# belt_output.net
KiCad netlist of a schematic drawn in Altium Designer
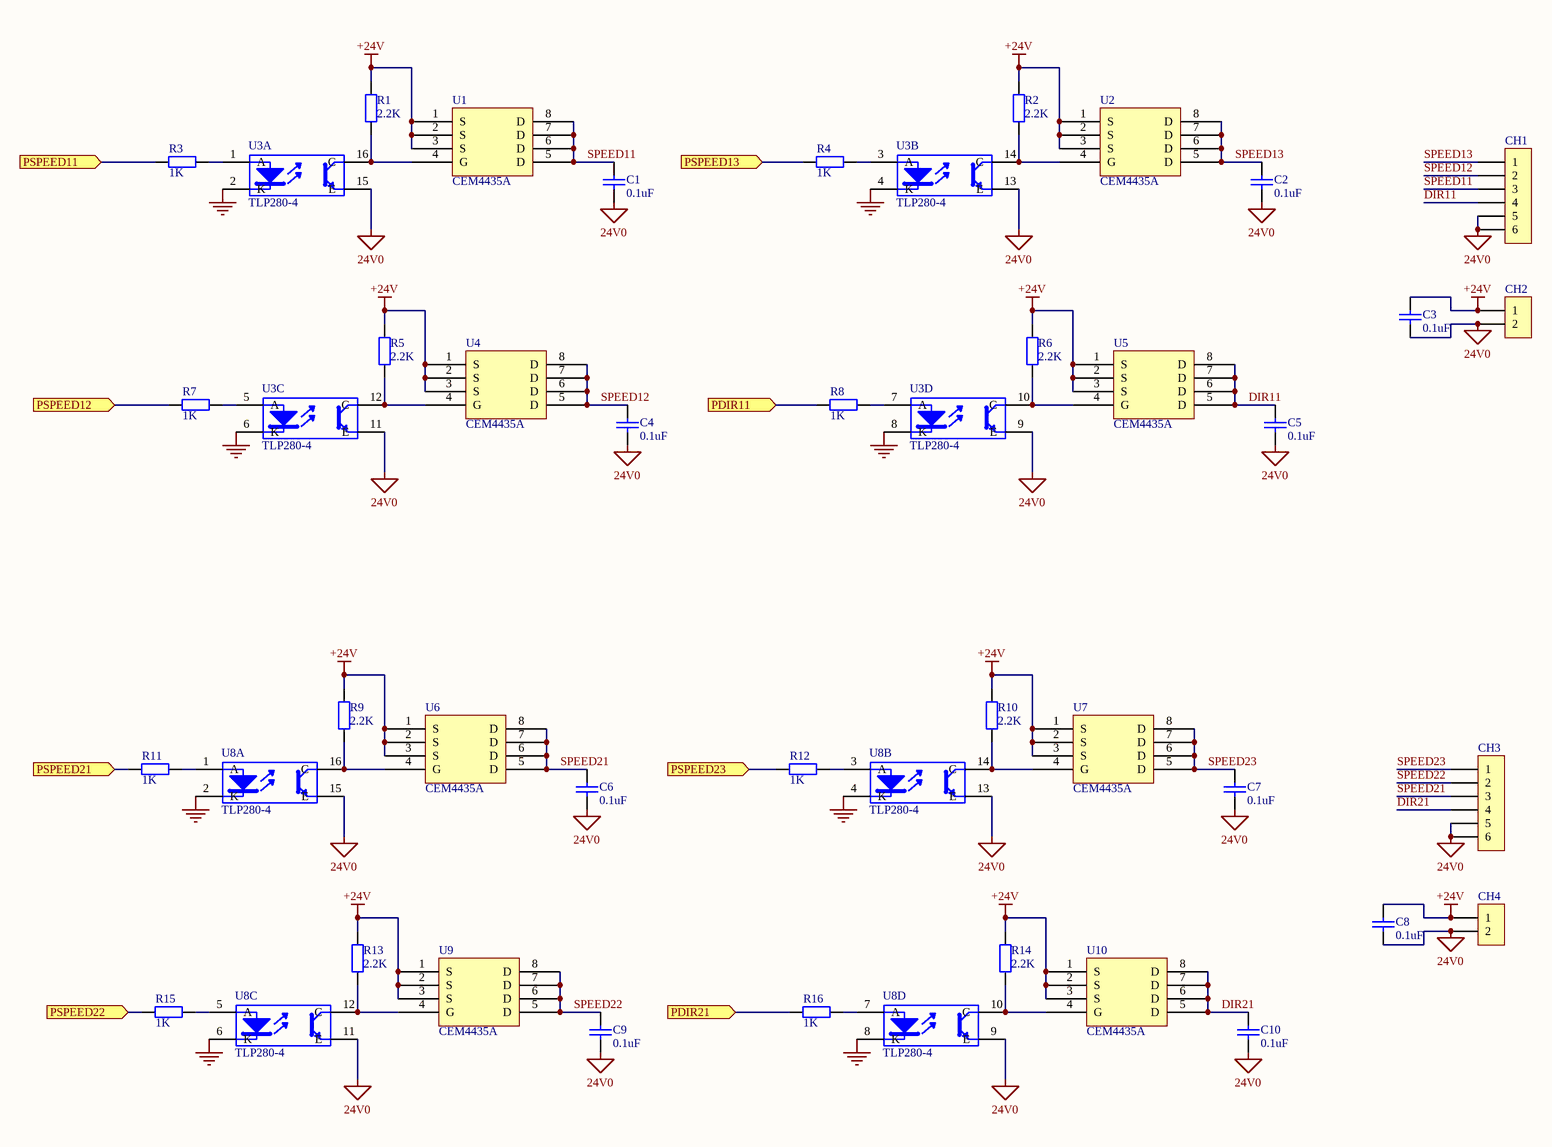
[diagram p0: belt_output.SchDoc]

(export (version "E")
  (design (tool "Eeschema 10.0.6"))
  (components
    (comp (ref "C1")
      (value "0.1uF")
      (footprint "0805")
      (description "Capacitor")
      (fields (field (name "Comment") "Cap") (field (name "PUBLISHER") "Altium Limited"))
      (libsource (lib "Miscellaneous Devices") (part "Cap"))
    )
    (comp (ref "C2")
      (value "0.1uF")
      (footprint "0805")
      (description "Capacitor")
      (fields (field (name "Comment") "Cap") (field (name "PUBLISHER") "Altium Limited"))
      (libsource (lib "Miscellaneous Devices") (part "Cap"))
    )
    (comp (ref "C3")
      (value "0.1uF")
      (footprint "0805")
      (description "Capacitor")
      (fields (field (name "Comment") "Cap") (field (name "PUBLISHER") "Altium Limited"))
      (libsource (lib "Miscellaneous Devices") (part "Cap"))
    )
    (comp (ref "C4")
      (value "0.1uF")
      (footprint "0805")
      (description "Capacitor")
      (fields (field (name "Comment") "Cap") (field (name "PUBLISHER") "Altium Limited"))
      (libsource (lib "Miscellaneous Devices") (part "Cap"))
    )
    (comp (ref "C5")
      (value "0.1uF")
      (footprint "0805")
      (description "Capacitor")
      (fields (field (name "Comment") "Cap") (field (name "PUBLISHER") "Altium Limited"))
      (libsource (lib "Miscellaneous Devices") (part "Cap"))
    )
    (comp (ref "C6")
      (value "0.1uF")
      (footprint "0805")
      (description "Capacitor")
      (fields (field (name "Comment") "Cap") (field (name "PUBLISHER") "Altium Limited"))
      (libsource (lib "Miscellaneous Devices") (part "Cap"))
    )
    (comp (ref "C7")
      (value "0.1uF")
      (footprint "0805")
      (description "Capacitor")
      (fields (field (name "Comment") "Cap") (field (name "PUBLISHER") "Altium Limited"))
      (libsource (lib "Miscellaneous Devices") (part "Cap"))
    )
    (comp (ref "C8")
      (value "0.1uF")
      (footprint "0805")
      (description "Capacitor")
      (fields (field (name "Comment") "Cap") (field (name "PUBLISHER") "Altium Limited"))
      (libsource (lib "Miscellaneous Devices") (part "Cap"))
    )
    (comp (ref "C9")
      (value "0.1uF")
      (footprint "0805")
      (description "Capacitor")
      (fields (field (name "Comment") "Cap") (field (name "PUBLISHER") "Altium Limited"))
      (libsource (lib "Miscellaneous Devices") (part "Cap"))
    )
    (comp (ref "C10")
      (value "0.1uF")
      (footprint "0805")
      (description "Capacitor")
      (fields (field (name "Comment") "Cap") (field (name "PUBLISHER") "Altium Limited"))
      (libsource (lib "Miscellaneous Devices") (part "Cap"))
    )
    (comp (ref "CH1")
      (value "HEADER1X6")
      (footprint "CH3.96-6PIN")
      (libsource (lib "myIntegrated_Library1") (part "HEADER1X6"))
    )
    (comp (ref "CH2")
      (value "HEADER1X2")
      (footprint "CH3.96-2PIN")
      (libsource (lib "myIntegrated_Library1") (part "HEADER1X2"))
    )
    (comp (ref "CH3")
      (value "HEADER1X6")
      (footprint "CH3.96-6PIN")
      (libsource (lib "myIntegrated_Library1") (part "HEADER1X6"))
    )
    (comp (ref "CH4")
      (value "HEADER1X2")
      (footprint "CH3.96-2PIN")
      (libsource (lib "myIntegrated_Library1") (part "HEADER1X2"))
    )
    (comp (ref "R1")
      (value "2.2K")
      (footprint "0805")
      (description "Resistor")
      (fields (field (name "Comment") "Res2") (field (name "PUBLISHER") "Altium Limited"))
      (libsource (lib "Miscellaneous Devices") (part "Res2"))
    )
    (comp (ref "R2")
      (value "2.2K")
      (footprint "0805")
      (description "Resistor")
      (fields (field (name "Comment") "Res2") (field (name "PUBLISHER") "Altium Limited"))
      (libsource (lib "Miscellaneous Devices") (part "Res2"))
    )
    (comp (ref "R3")
      (value "1K")
      (footprint "0805")
      (description "Resistor")
      (fields (field (name "Comment") "Res2") (field (name "PUBLISHER") "Altium Limited"))
      (libsource (lib "") (part "Res2_1"))
    )
    (comp (ref "R4")
      (value "1K")
      (footprint "0805")
      (description "Resistor")
      (fields (field (name "Comment") "Res2") (field (name "PUBLISHER") "Altium Limited"))
      (libsource (lib "") (part "Res2_1"))
    )
    (comp (ref "R5")
      (value "2.2K")
      (footprint "0805")
      (description "Resistor")
      (fields (field (name "Comment") "Res2") (field (name "PUBLISHER") "Altium Limited"))
      (libsource (lib "Miscellaneous Devices") (part "Res2"))
    )
    (comp (ref "R6")
      (value "2.2K")
      (footprint "0805")
      (description "Resistor")
      (fields (field (name "Comment") "Res2") (field (name "PUBLISHER") "Altium Limited"))
      (libsource (lib "Miscellaneous Devices") (part "Res2"))
    )
    (comp (ref "R7")
      (value "1K")
      (footprint "0805")
      (description "Resistor")
      (fields (field (name "Comment") "Res2") (field (name "PUBLISHER") "Altium Limited"))
      (libsource (lib "") (part "Res2_1"))
    )
    (comp (ref "R8")
      (value "1K")
      (footprint "0805")
      (description "Resistor")
      (fields (field (name "Comment") "Res2") (field (name "PUBLISHER") "Altium Limited"))
      (libsource (lib "") (part "Res2_1"))
    )
    (comp (ref "R9")
      (value "2.2K")
      (footprint "0805")
      (description "Resistor")
      (fields (field (name "Comment") "Res2") (field (name "PUBLISHER") "Altium Limited"))
      (libsource (lib "Miscellaneous Devices") (part "Res2"))
    )
    (comp (ref "R10")
      (value "2.2K")
      (footprint "0805")
      (description "Resistor")
      (fields (field (name "Comment") "Res2") (field (name "PUBLISHER") "Altium Limited"))
      (libsource (lib "Miscellaneous Devices") (part "Res2"))
    )
    (comp (ref "R11")
      (value "1K")
      (footprint "0805")
      (description "Resistor")
      (fields (field (name "Comment") "Res2") (field (name "PUBLISHER") "Altium Limited"))
      (libsource (lib "") (part "Res2_1"))
    )
    (comp (ref "R12")
      (value "1K")
      (footprint "0805")
      (description "Resistor")
      (fields (field (name "Comment") "Res2") (field (name "PUBLISHER") "Altium Limited"))
      (libsource (lib "") (part "Res2_1"))
    )
    (comp (ref "R13")
      (value "2.2K")
      (footprint "0805")
      (description "Resistor")
      (fields (field (name "Comment") "Res2") (field (name "PUBLISHER") "Altium Limited"))
      (libsource (lib "Miscellaneous Devices") (part "Res2"))
    )
    (comp (ref "R14")
      (value "2.2K")
      (footprint "0805")
      (description "Resistor")
      (fields (field (name "Comment") "Res2") (field (name "PUBLISHER") "Altium Limited"))
      (libsource (lib "Miscellaneous Devices") (part "Res2"))
    )
    (comp (ref "R15")
      (value "1K")
      (footprint "0805")
      (description "Resistor")
      (fields (field (name "Comment") "Res2") (field (name "PUBLISHER") "Altium Limited"))
      (libsource (lib "") (part "Res2_1"))
    )
    (comp (ref "R16")
      (value "1K")
      (footprint "0805")
      (description "Resistor")
      (fields (field (name "Comment") "Res2") (field (name "PUBLISHER") "Altium Limited"))
      (libsource (lib "") (part "Res2_1"))
    )
    (comp (ref "U1")
      (value "CEM4435A")
      (footprint "SOP8-OP27")
      (libsource (lib "myIntegrated_Library1") (part "CEM4435A"))
    )
    (comp (ref "U2")
      (value "CEM4435A")
      (footprint "SOP8-OP27")
      (libsource (lib "myIntegrated_Library1") (part "CEM4435A"))
    )
    (comp (ref "U3") (value "TLP280-4") (footprint "SO16") (libsource (lib "WH V20") (part "TLP521-4")))
    (comp (ref "U4")
      (value "CEM4435A")
      (footprint "SOP8-OP27")
      (libsource (lib "myIntegrated_Library1") (part "CEM4435A"))
    )
    (comp (ref "U5")
      (value "CEM4435A")
      (footprint "SOP8-OP27")
      (libsource (lib "myIntegrated_Library1") (part "CEM4435A"))
    )
    (comp (ref "U6")
      (value "CEM4435A")
      (footprint "SOP8-OP27")
      (libsource (lib "myIntegrated_Library1") (part "CEM4435A"))
    )
    (comp (ref "U7")
      (value "CEM4435A")
      (footprint "SOP8-OP27")
      (libsource (lib "myIntegrated_Library1") (part "CEM4435A"))
    )
    (comp (ref "U8") (value "TLP280-4") (footprint "SO16") (libsource (lib "WH V20") (part "TLP521-4")))
    (comp (ref "U9")
      (value "CEM4435A")
      (footprint "SOP8-OP27")
      (libsource (lib "myIntegrated_Library1") (part "CEM4435A"))
    )
    (comp (ref "U10")
      (value "CEM4435A")
      (footprint "SOP8-OP27")
      (libsource (lib "myIntegrated_Library1") (part "CEM4435A"))
    )
  )
  (nets
    (net (code "1") (name "+24V") (class "Default")
      (node (ref "C3") (pin "1") (pinfunction "1_1") (pintype "passive"))
      (node (ref "C8") (pin "1") (pinfunction "1_1") (pintype "passive"))
      (node (ref "CH2") (pin "1") (pinfunction "1_1") (pintype "passive"))
      (node (ref "CH4") (pin "1") (pinfunction "1_1") (pintype "passive"))
      (node (ref "R1") (pin "2") (pinfunction "2_2") (pintype "passive"))
      (node (ref "R10") (pin "2") (pinfunction "2_2") (pintype "passive"))
      (node (ref "R13") (pin "2") (pinfunction "2_2") (pintype "passive"))
      (node (ref "R14") (pin "2") (pinfunction "2_2") (pintype "passive"))
      (node (ref "R2") (pin "2") (pinfunction "2_2") (pintype "passive"))
      (node (ref "R5") (pin "2") (pinfunction "2_2") (pintype "passive"))
      (node (ref "R6") (pin "2") (pinfunction "2_2") (pintype "passive"))
      (node (ref "R9") (pin "2") (pinfunction "2_2") (pintype "passive"))
      (node (ref "U1") (pin "1") (pinfunction "S_1") (pintype "passive"))
      (node (ref "U1") (pin "2") (pinfunction "S_2") (pintype "passive"))
      (node (ref "U1") (pin "3") (pinfunction "S_3") (pintype "passive"))
      (node (ref "U10") (pin "1") (pinfunction "S_1") (pintype "passive"))
      (node (ref "U10") (pin "2") (pinfunction "S_2") (pintype "passive"))
      (node (ref "U10") (pin "3") (pinfunction "S_3") (pintype "passive"))
      (node (ref "U2") (pin "1") (pinfunction "S_1") (pintype "passive"))
      (node (ref "U2") (pin "2") (pinfunction "S_2") (pintype "passive"))
      (node (ref "U2") (pin "3") (pinfunction "S_3") (pintype "passive"))
      (node (ref "U4") (pin "1") (pinfunction "S_1") (pintype "passive"))
      (node (ref "U4") (pin "2") (pinfunction "S_2") (pintype "passive"))
      (node (ref "U4") (pin "3") (pinfunction "S_3") (pintype "passive"))
      (node (ref "U5") (pin "1") (pinfunction "S_1") (pintype "passive"))
      (node (ref "U5") (pin "2") (pinfunction "S_2") (pintype "passive"))
      (node (ref "U5") (pin "3") (pinfunction "S_3") (pintype "passive"))
      (node (ref "U6") (pin "1") (pinfunction "S_1") (pintype "passive"))
      (node (ref "U6") (pin "2") (pinfunction "S_2") (pintype "passive"))
      (node (ref "U6") (pin "3") (pinfunction "S_3") (pintype "passive"))
      (node (ref "U7") (pin "1") (pinfunction "S_1") (pintype "passive"))
      (node (ref "U7") (pin "2") (pinfunction "S_2") (pintype "passive"))
      (node (ref "U7") (pin "3") (pinfunction "S_3") (pintype "passive"))
      (node (ref "U9") (pin "1") (pinfunction "S_1") (pintype "passive"))
      (node (ref "U9") (pin "2") (pinfunction "S_2") (pintype "passive"))
      (node (ref "U9") (pin "3") (pinfunction "S_3") (pintype "passive"))
    )
    (net (code "2") (name "/DIR11") (class "Default")
      (node (ref "C5") (pin "1") (pinfunction "1_1") (pintype "passive"))
      (node (ref "CH1") (pin "4") (pinfunction "4_4") (pintype "passive"))
      (node (ref "U5") (pin "5") (pinfunction "D_5") (pintype "passive"))
      (node (ref "U5") (pin "6") (pinfunction "D_6") (pintype "passive"))
      (node (ref "U5") (pin "7") (pinfunction "D_7") (pintype "passive"))
      (node (ref "U5") (pin "8") (pinfunction "D_8") (pintype "passive"))
    )
    (net (code "3") (name "/DIR21") (class "Default")
      (node (ref "C10") (pin "1") (pinfunction "1_1") (pintype "passive"))
      (node (ref "CH3") (pin "4") (pinfunction "4_4") (pintype "passive"))
      (node (ref "U10") (pin "5") (pinfunction "D_5") (pintype "passive"))
      (node (ref "U10") (pin "6") (pinfunction "D_6") (pintype "passive"))
      (node (ref "U10") (pin "7") (pinfunction "D_7") (pintype "passive"))
      (node (ref "U10") (pin "8") (pinfunction "D_8") (pintype "passive"))
    )
    (net (code "4") (name "/PDIR11") (class "Default")
      (node (ref "R8") (pin "1") (pinfunction "1_1") (pintype "passive"))
    )
    (net (code "5") (name "/PDIR21") (class "Default")
      (node (ref "R16") (pin "1") (pinfunction "1_1") (pintype "passive"))
    )
    (net (code "6") (name "/PSPEED11") (class "Default")
      (node (ref "R3") (pin "1") (pinfunction "1_1") (pintype "passive"))
    )
    (net (code "7") (name "/PSPEED12") (class "Default")
      (node (ref "R7") (pin "1") (pinfunction "1_1") (pintype "passive"))
    )
    (net (code "8") (name "/PSPEED13") (class "Default")
      (node (ref "R4") (pin "1") (pinfunction "1_1") (pintype "passive"))
    )
    (net (code "9") (name "/PSPEED21") (class "Default")
      (node (ref "R11") (pin "1") (pinfunction "1_1") (pintype "passive"))
    )
    (net (code "10") (name "/PSPEED22") (class "Default")
      (node (ref "R15") (pin "1") (pinfunction "1_1") (pintype "passive"))
    )
    (net (code "11") (name "/PSPEED23") (class "Default")
      (node (ref "R12") (pin "1") (pinfunction "1_1") (pintype "passive"))
    )
    (net (code "12") (name "/SPEED11") (class "Default")
      (node (ref "C1") (pin "1") (pinfunction "1_1") (pintype "passive"))
      (node (ref "CH1") (pin "3") (pinfunction "3_3") (pintype "passive"))
      (node (ref "U1") (pin "5") (pinfunction "D_5") (pintype "passive"))
      (node (ref "U1") (pin "6") (pinfunction "D_6") (pintype "passive"))
      (node (ref "U1") (pin "7") (pinfunction "D_7") (pintype "passive"))
      (node (ref "U1") (pin "8") (pinfunction "D_8") (pintype "passive"))
    )
    (net (code "13") (name "/SPEED12") (class "Default")
      (node (ref "C4") (pin "1") (pinfunction "1_1") (pintype "passive"))
      (node (ref "CH1") (pin "2") (pinfunction "2_2") (pintype "passive"))
      (node (ref "U4") (pin "5") (pinfunction "D_5") (pintype "passive"))
      (node (ref "U4") (pin "6") (pinfunction "D_6") (pintype "passive"))
      (node (ref "U4") (pin "7") (pinfunction "D_7") (pintype "passive"))
      (node (ref "U4") (pin "8") (pinfunction "D_8") (pintype "passive"))
    )
    (net (code "14") (name "/SPEED13") (class "Default")
      (node (ref "C2") (pin "1") (pinfunction "1_1") (pintype "passive"))
      (node (ref "CH1") (pin "1") (pinfunction "1_1") (pintype "passive"))
      (node (ref "U2") (pin "5") (pinfunction "D_5") (pintype "passive"))
      (node (ref "U2") (pin "6") (pinfunction "D_6") (pintype "passive"))
      (node (ref "U2") (pin "7") (pinfunction "D_7") (pintype "passive"))
      (node (ref "U2") (pin "8") (pinfunction "D_8") (pintype "passive"))
    )
    (net (code "15") (name "/SPEED21") (class "Default")
      (node (ref "C6") (pin "1") (pinfunction "1_1") (pintype "passive"))
      (node (ref "CH3") (pin "3") (pinfunction "3_3") (pintype "passive"))
      (node (ref "U6") (pin "5") (pinfunction "D_5") (pintype "passive"))
      (node (ref "U6") (pin "6") (pinfunction "D_6") (pintype "passive"))
      (node (ref "U6") (pin "7") (pinfunction "D_7") (pintype "passive"))
      (node (ref "U6") (pin "8") (pinfunction "D_8") (pintype "passive"))
    )
    (net (code "16") (name "/SPEED22") (class "Default")
      (node (ref "C9") (pin "1") (pinfunction "1_1") (pintype "passive"))
      (node (ref "CH3") (pin "2") (pinfunction "2_2") (pintype "passive"))
      (node (ref "U9") (pin "5") (pinfunction "D_5") (pintype "passive"))
      (node (ref "U9") (pin "6") (pinfunction "D_6") (pintype "passive"))
      (node (ref "U9") (pin "7") (pinfunction "D_7") (pintype "passive"))
      (node (ref "U9") (pin "8") (pinfunction "D_8") (pintype "passive"))
    )
    (net (code "17") (name "/SPEED23") (class "Default")
      (node (ref "C7") (pin "1") (pinfunction "1_1") (pintype "passive"))
      (node (ref "CH3") (pin "1") (pinfunction "1_1") (pintype "passive"))
      (node (ref "U7") (pin "5") (pinfunction "D_5") (pintype "passive"))
      (node (ref "U7") (pin "6") (pinfunction "D_6") (pintype "passive"))
      (node (ref "U7") (pin "7") (pinfunction "D_7") (pintype "passive"))
      (node (ref "U7") (pin "8") (pinfunction "D_8") (pintype "passive"))
    )
    (net (code "18") (name "24V0") (class "Default")
      (node (ref "C1") (pin "2") (pinfunction "2_2") (pintype "passive"))
      (node (ref "C10") (pin "2") (pinfunction "2_2") (pintype "passive"))
      (node (ref "C2") (pin "2") (pinfunction "2_2") (pintype "passive"))
      (node (ref "C3") (pin "2") (pinfunction "2_2") (pintype "passive"))
      (node (ref "C4") (pin "2") (pinfunction "2_2") (pintype "passive"))
      (node (ref "C5") (pin "2") (pinfunction "2_2") (pintype "passive"))
      (node (ref "C6") (pin "2") (pinfunction "2_2") (pintype "passive"))
      (node (ref "C7") (pin "2") (pinfunction "2_2") (pintype "passive"))
      (node (ref "C8") (pin "2") (pinfunction "2_2") (pintype "passive"))
      (node (ref "C9") (pin "2") (pinfunction "2_2") (pintype "passive"))
      (node (ref "CH1") (pin "5") (pinfunction "5_5") (pintype "passive"))
      (node (ref "CH1") (pin "6") (pinfunction "6_6") (pintype "passive"))
      (node (ref "CH2") (pin "2") (pinfunction "2_2") (pintype "passive"))
      (node (ref "CH3") (pin "5") (pinfunction "5_5") (pintype "passive"))
      (node (ref "CH3") (pin "6") (pinfunction "6_6") (pintype "passive"))
      (node (ref "CH4") (pin "2") (pinfunction "2_2") (pintype "passive"))
      (node (ref "U3") (pin "11") (pinfunction "E_11") (pintype "passive"))
      (node (ref "U3") (pin "13") (pinfunction "E_13") (pintype "passive"))
      (node (ref "U3") (pin "15") (pinfunction "E_15") (pintype "passive"))
      (node (ref "U3") (pin "9") (pinfunction "E_9") (pintype "passive"))
      (node (ref "U8") (pin "11") (pinfunction "E_11") (pintype "passive"))
      (node (ref "U8") (pin "13") (pinfunction "E_13") (pintype "passive"))
      (node (ref "U8") (pin "15") (pinfunction "E_15") (pintype "passive"))
      (node (ref "U8") (pin "9") (pinfunction "E_9") (pintype "passive"))
    )
    (net (code "19") (name "GND") (class "Default")
      (node (ref "U3") (pin "2") (pinfunction "K_2") (pintype "passive"))
      (node (ref "U3") (pin "4") (pinfunction "K_4") (pintype "passive"))
      (node (ref "U3") (pin "6") (pinfunction "K_6") (pintype "passive"))
      (node (ref "U3") (pin "8") (pinfunction "K_8") (pintype "passive"))
      (node (ref "U8") (pin "2") (pinfunction "K_2") (pintype "passive"))
      (node (ref "U8") (pin "4") (pinfunction "K_4") (pintype "passive"))
      (node (ref "U8") (pin "6") (pinfunction "K_6") (pintype "passive"))
      (node (ref "U8") (pin "8") (pinfunction "K_8") (pintype "passive"))
    )
    (net (code "20") (name "Net-(U1-G)") (class "Default")
      (node (ref "R1") (pin "1") (pinfunction "1_1") (pintype "passive"))
      (node (ref "U1") (pin "4") (pinfunction "G_4") (pintype "passive"))
      (node (ref "U3") (pin "16") (pinfunction "C_16") (pintype "passive"))
    )
    (net (code "21") (name "Net-(U2-G)") (class "Default")
      (node (ref "R2") (pin "1") (pinfunction "1_1") (pintype "passive"))
      (node (ref "U2") (pin "4") (pinfunction "G_4") (pintype "passive"))
      (node (ref "U3") (pin "14") (pinfunction "C_14") (pintype "passive"))
    )
    (net (code "22") (name "Net-(U3A-A)") (class "Default")
      (node (ref "R3") (pin "2") (pinfunction "2_2") (pintype "passive"))
      (node (ref "U3") (pin "1") (pinfunction "A_1") (pintype "passive"))
    )
    (net (code "23") (name "Net-(U3B-A)") (class "Default")
      (node (ref "R4") (pin "2") (pinfunction "2_2") (pintype "passive"))
      (node (ref "U3") (pin "3") (pinfunction "A_3") (pintype "passive"))
    )
    (net (code "24") (name "Net-(U3C-A)") (class "Default")
      (node (ref "R7") (pin "2") (pinfunction "2_2") (pintype "passive"))
      (node (ref "U3") (pin "5") (pinfunction "A_5") (pintype "passive"))
    )
    (net (code "25") (name "Net-(U3C-C)") (class "Default")
      (node (ref "R5") (pin "1") (pinfunction "1_1") (pintype "passive"))
      (node (ref "U3") (pin "12") (pinfunction "C_12") (pintype "passive"))
      (node (ref "U4") (pin "4") (pinfunction "G_4") (pintype "passive"))
    )
    (net (code "26") (name "Net-(U3D-A)") (class "Default")
      (node (ref "R8") (pin "2") (pinfunction "2_2") (pintype "passive"))
      (node (ref "U3") (pin "7") (pinfunction "A_7") (pintype "passive"))
    )
    (net (code "27") (name "Net-(U3D-C)") (class "Default")
      (node (ref "R6") (pin "1") (pinfunction "1_1") (pintype "passive"))
      (node (ref "U3") (pin "10") (pinfunction "C_10") (pintype "passive"))
      (node (ref "U5") (pin "4") (pinfunction "G_4") (pintype "passive"))
    )
    (net (code "28") (name "Net-(U6-G)") (class "Default")
      (node (ref "R9") (pin "1") (pinfunction "1_1") (pintype "passive"))
      (node (ref "U6") (pin "4") (pinfunction "G_4") (pintype "passive"))
      (node (ref "U8") (pin "16") (pinfunction "C_16") (pintype "passive"))
    )
    (net (code "29") (name "Net-(U7-G)") (class "Default")
      (node (ref "R10") (pin "1") (pinfunction "1_1") (pintype "passive"))
      (node (ref "U7") (pin "4") (pinfunction "G_4") (pintype "passive"))
      (node (ref "U8") (pin "14") (pinfunction "C_14") (pintype "passive"))
    )
    (net (code "30") (name "Net-(U8A-A)") (class "Default")
      (node (ref "R11") (pin "2") (pinfunction "2_2") (pintype "passive"))
      (node (ref "U8") (pin "1") (pinfunction "A_1") (pintype "passive"))
    )
    (net (code "31") (name "Net-(U8B-A)") (class "Default")
      (node (ref "R12") (pin "2") (pinfunction "2_2") (pintype "passive"))
      (node (ref "U8") (pin "3") (pinfunction "A_3") (pintype "passive"))
    )
    (net (code "32") (name "Net-(U8C-A)") (class "Default")
      (node (ref "R15") (pin "2") (pinfunction "2_2") (pintype "passive"))
      (node (ref "U8") (pin "5") (pinfunction "A_5") (pintype "passive"))
    )
    (net (code "33") (name "Net-(U8C-C)") (class "Default")
      (node (ref "R13") (pin "1") (pinfunction "1_1") (pintype "passive"))
      (node (ref "U8") (pin "12") (pinfunction "C_12") (pintype "passive"))
      (node (ref "U9") (pin "4") (pinfunction "G_4") (pintype "passive"))
    )
    (net (code "34") (name "Net-(U8D-A)") (class "Default")
      (node (ref "R16") (pin "2") (pinfunction "2_2") (pintype "passive"))
      (node (ref "U8") (pin "7") (pinfunction "A_7") (pintype "passive"))
    )
    (net (code "35") (name "Net-(U10-G)") (class "Default")
      (node (ref "R14") (pin "1") (pinfunction "1_1") (pintype "passive"))
      (node (ref "U10") (pin "4") (pinfunction "G_4") (pintype "passive"))
      (node (ref "U8") (pin "10") (pinfunction "C_10") (pintype "passive"))
    )
  )
)
